# PowerSupply.net
KiCad netlist of a schematic drawn in Altium Designer
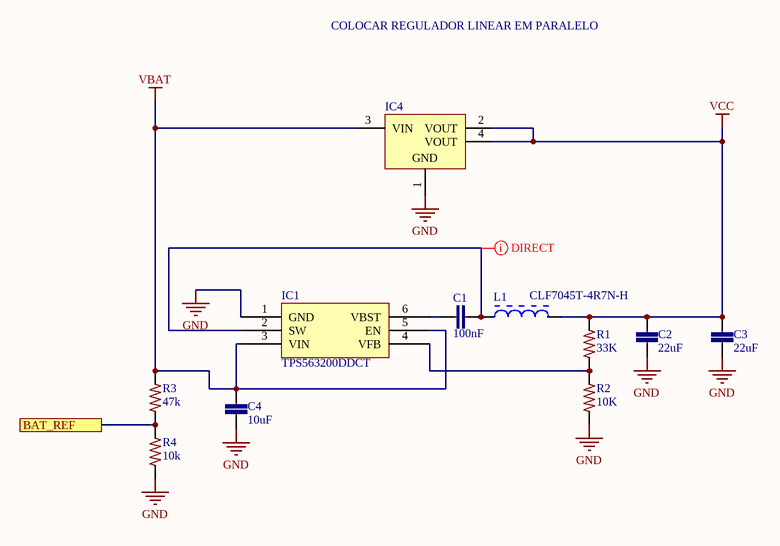
[diagram p0: PowerSupply.SchDoc]

(export (version "E")
  (design (tool "Eeschema 10.0.6"))
  (components
    (comp (ref "C1")
      (value "100nF")
      (footprint "0402-CAP")
      (description "CAP CER 0.1UF 50V 10% X7R 0402")
      (fields (field (name "PART NO") "C1005X7R1H104K050BB"))
      (libsource (lib "IMBEL") (part "CAPACITOR"))
    )
    (comp (ref "C2")
      (value "22uF")
      (footprint "1206-CAP")
      (description "CAP CER 22UF 6.3V 20% X5R 1206")
      (fields (field (name "PART NO") "C3216X5R0J226M085AC"))
      (libsource (lib "IMBEL") (part "CC1206-22uF-6.3V-1"))
    )
    (comp (ref "C3")
      (value "22uF")
      (footprint "1206-CAP")
      (description "CAP CER 22UF 6.3V 20% X5R 1206")
      (fields (field (name "PART NO") "C3216X5R0J226M085AC"))
      (libsource (lib "IMBEL") (part "CC1206-22uF-6.3V-1"))
    )
    (comp (ref "C4")
      (value "10uF")
      (footprint "1210-CAP")
      (description "CAP CER 10UF 50V 20% X5R 1210")
      (fields (field (name "PART NO") "UMK325BJ106MM"))
      (libsource (lib "") (part "CAPACITOR_1"))
    )
    (comp (ref "IC1")
      (value "TPS563200DDCT")
      (footprint "SOT95P280X110-6N")
      (description "IC REG BUCK ADJ 3A SYNC 6SOT")
      (libsource (lib "IMBEL") (part "Component_1"))
    )
    (comp (ref "IC4")
      (value "LD1117S33CTR")
      (footprint "SOT-223_N")
      (description "Fixed Low Drop Positive Voltage Regulator, 3.3V, 4-Pin SOT-223, Tape and Reel")
      (libsource (lib "Altium Content Vault") (part "CMP-0244-00307-1"))
    )
    (comp (ref "L1")
      (value "CLF7045T-4R7N-H")
      (footprint "CLF7045T")
      (description "FIXED IND 4.7UH 4.1A 20 MOHM SMD")
      (libsource (lib "IMBEL") (part "SRP1235"))
    )
    (comp (ref "R1")
      (value "33K")
      (footprint "0402-RES-HD")
      (description "RES 33K OHM 1/10W 1% 0402 SMD")
      (fields (field (name "PART NO") "ERJ-2RKF3302X"))
      (libsource (lib "IMBEL") (part "RESISTOR"))
    )
    (comp (ref "R2")
      (value "10K")
      (footprint "0402-RES-HD")
      (description "RES 10K OHM 1/10W 1% 0402 SMD")
      (fields (field (name "PART NO") "ERJ-2RKF1002X"))
      (libsource (lib "IMBEL") (part "R0402-10K-10"))
    )
    (comp (ref "R3")
      (value "47k")
      (footprint "0402-RES-HD")
      (description "RES 47k OHM 1/10W 1% 0402 SMD")
      (fields (field (name "PART NO") "ERJ-2RKF1002X"))
      (libsource (lib "IMBEL") (part "R0402-10K-10"))
    )
    (comp (ref "R4")
      (value "10k")
      (footprint "0402-RES-HD")
      (description "RES 10k OHM 1/10W 1% 0402 SMD")
      (fields (field (name "PART NO") "ERJ-2RKF3302X"))
      (libsource (lib "IMBEL") (part "R0402-33K-7"))
    )
  )
  (nets
    (net (code "1") (name "/BAT_REF") (class "Default")
      (node (ref "R3") (pin "1") (pinfunction "1_1") (pintype "passive"))
      (node (ref "R4") (pin "2") (pinfunction "2_2") (pintype "passive"))
    )
    (net (code "2") (name "GND") (class "Default")
      (node (ref "C2") (pin "1") (pinfunction "1_1") (pintype "passive"))
      (node (ref "C3") (pin "1") (pinfunction "1_1") (pintype "passive"))
      (node (ref "C4") (pin "1") (pinfunction "1_1") (pintype "passive"))
      (node (ref "IC1") (pin "1") (pinfunction "GND_1") (pintype "passive"))
      (node (ref "IC4") (pin "1") (pinfunction "GND_1") (pintype "power_in"))
      (node (ref "R2") (pin "1") (pinfunction "1_1") (pintype "passive"))
      (node (ref "R4") (pin "1") (pinfunction "1_1") (pintype "passive"))
    )
    (net (code "3") (name "Net-(IC1-SW)") (class "Default")
      (node (ref "C1") (pin "2") (pinfunction "2_2") (pintype "passive"))
      (node (ref "IC1") (pin "2") (pinfunction "SW_2") (pintype "passive"))
      (node (ref "L1") (pin "1") (pinfunction "1_1") (pintype "passive"))
    )
    (net (code "4") (name "Net-(IC1-VBST)") (class "Default")
      (node (ref "C1") (pin "1") (pinfunction "1_1") (pintype "passive"))
      (node (ref "IC1") (pin "6") (pinfunction "VBST_6") (pintype "passive"))
    )
    (net (code "5") (name "Net-(IC1-VFB)") (class "Default")
      (node (ref "IC1") (pin "4") (pinfunction "VFB_4") (pintype "passive"))
      (node (ref "R1") (pin "1") (pinfunction "1_1") (pintype "passive"))
      (node (ref "R2") (pin "2") (pinfunction "2_2") (pintype "passive"))
    )
    (net (code "6") (name "VBAT") (class "Default")
      (node (ref "C4") (pin "2") (pinfunction "2_2") (pintype "passive"))
      (node (ref "IC1") (pin "3") (pinfunction "VIN_3") (pintype "passive"))
      (node (ref "IC1") (pin "5") (pinfunction "EN_5") (pintype "passive"))
      (node (ref "IC4") (pin "3") (pinfunction "VIN_3") (pintype "power_in"))
      (node (ref "R3") (pin "2") (pinfunction "2_2") (pintype "passive"))
    )
    (net (code "7") (name "VCC") (class "Default")
      (node (ref "C2") (pin "2") (pinfunction "2_2") (pintype "passive"))
      (node (ref "C3") (pin "2") (pinfunction "2_2") (pintype "passive"))
      (node (ref "IC4") (pin "2") (pinfunction "VOUT_2") (pintype "power_in"))
      (node (ref "IC4") (pin "4") (pinfunction "VOUT_4") (pintype "power_in"))
      (node (ref "L1") (pin "2") (pinfunction "2_2") (pintype "passive"))
      (node (ref "R1") (pin "2") (pinfunction "2_2") (pintype "passive"))
    )
  )
)
